# PCB-BI16-2x8.net
KiCad netlist of a schematic drawn in EAGLE
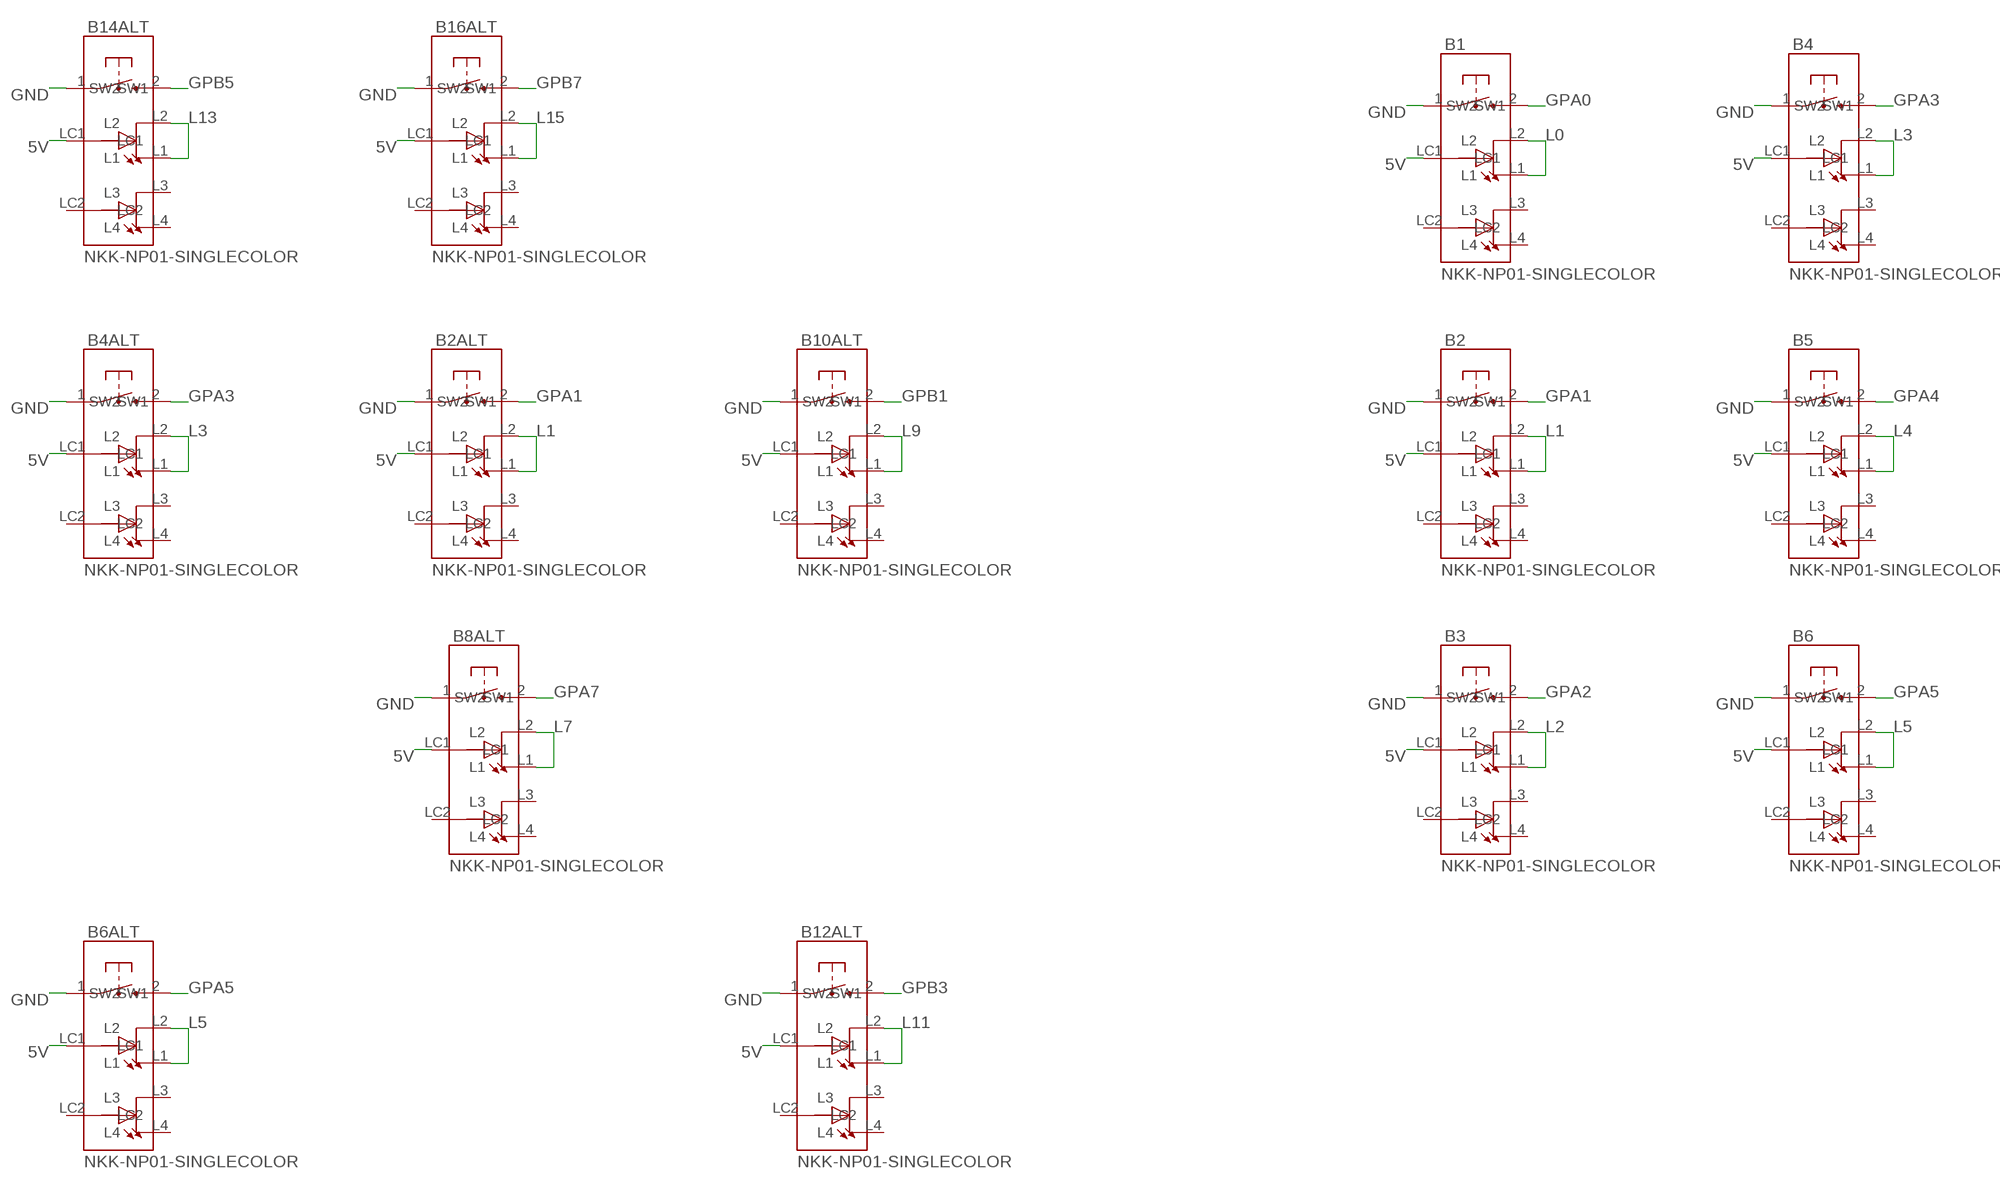
[diagram p0: schematic, sheet 1, part 1 of 2]
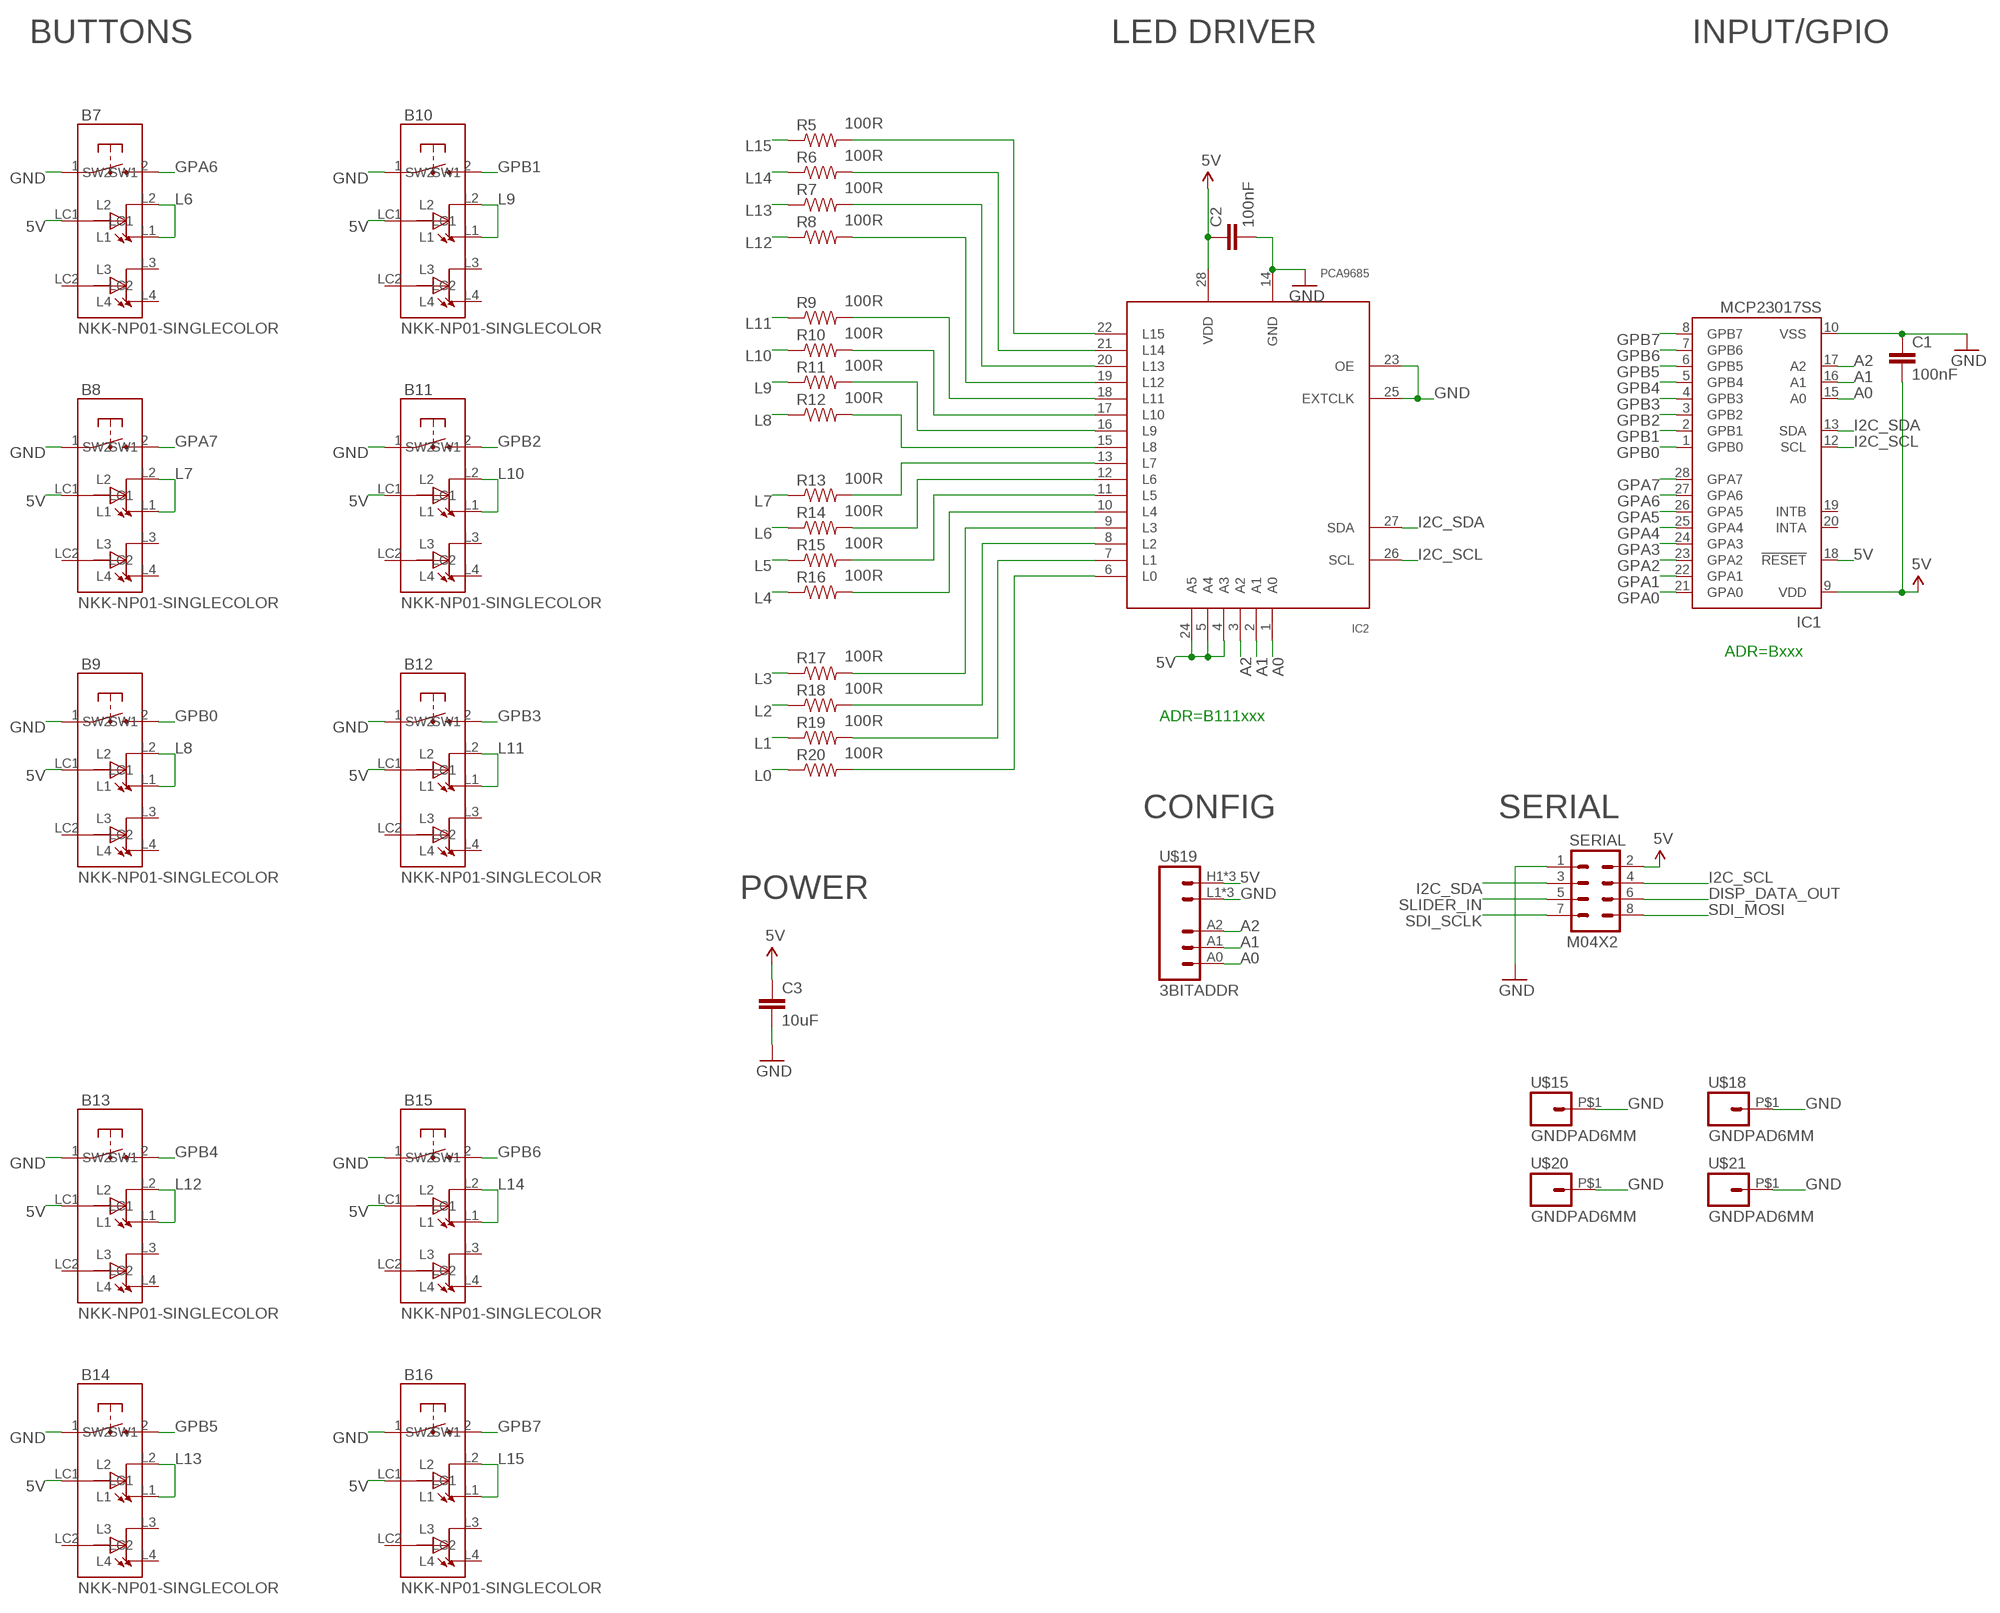
[diagram p1: schematic, sheet 1, part 2 of 2]

(export (version "E")
  (design (tool "Eeschema 10.0.6"))
  (components
    (comp (ref "B1")
      (value "NKK-NP01-SINGLECOLOR")
      (footprint "eagle-import:NKK-NP01")
      (libsource (lib "eagle-import") (part "NKK-NP01-SINGLECOLOR"))
    )
    (comp (ref "B2")
      (value "NKK-NP01-SINGLECOLOR")
      (footprint "eagle-import:NKK-NP01")
      (libsource (lib "eagle-import") (part "NKK-NP01-SINGLECOLOR"))
    )
    (comp (ref "B2ALT")
      (value "NKK-NP01-SINGLECOLOR")
      (footprint "eagle-import:NKK-NP01")
      (libsource (lib "eagle-import") (part "NKK-NP01-SINGLECOLOR"))
    )
    (comp (ref "B3")
      (value "NKK-NP01-SINGLECOLOR")
      (footprint "eagle-import:NKK-NP01")
      (libsource (lib "eagle-import") (part "NKK-NP01-SINGLECOLOR"))
    )
    (comp (ref "B4")
      (value "NKK-NP01-SINGLECOLOR")
      (footprint "eagle-import:NKK-NP01")
      (libsource (lib "eagle-import") (part "NKK-NP01-SINGLECOLOR"))
    )
    (comp (ref "B4ALT")
      (value "NKK-NP01-SINGLECOLOR")
      (footprint "eagle-import:NKK-NP01")
      (libsource (lib "eagle-import") (part "NKK-NP01-SINGLECOLOR"))
    )
    (comp (ref "B5")
      (value "NKK-NP01-SINGLECOLOR")
      (footprint "eagle-import:NKK-NP01")
      (libsource (lib "eagle-import") (part "NKK-NP01-SINGLECOLOR"))
    )
    (comp (ref "B6")
      (value "NKK-NP01-SINGLECOLOR")
      (footprint "eagle-import:NKK-NP01")
      (libsource (lib "eagle-import") (part "NKK-NP01-SINGLECOLOR"))
    )
    (comp (ref "B6ALT")
      (value "NKK-NP01-SINGLECOLOR")
      (footprint "eagle-import:NKK-NP01")
      (libsource (lib "eagle-import") (part "NKK-NP01-SINGLECOLOR"))
    )
    (comp (ref "B7")
      (value "NKK-NP01-SINGLECOLOR")
      (footprint "eagle-import:NKK-NP01")
      (libsource (lib "eagle-import") (part "NKK-NP01-SINGLECOLOR"))
    )
    (comp (ref "B8")
      (value "NKK-NP01-SINGLECOLOR")
      (footprint "eagle-import:NKK-NP01")
      (libsource (lib "eagle-import") (part "NKK-NP01-SINGLECOLOR"))
    )
    (comp (ref "B8ALT")
      (value "NKK-NP01-SINGLECOLOR")
      (footprint "eagle-import:NKK-NP01")
      (libsource (lib "eagle-import") (part "NKK-NP01-SINGLECOLOR"))
    )
    (comp (ref "B9")
      (value "NKK-NP01-SINGLECOLOR")
      (footprint "eagle-import:NKK-NP01")
      (libsource (lib "eagle-import") (part "NKK-NP01-SINGLECOLOR"))
    )
    (comp (ref "B10")
      (value "NKK-NP01-SINGLECOLOR")
      (footprint "eagle-import:NKK-NP01")
      (libsource (lib "eagle-import") (part "NKK-NP01-SINGLECOLOR"))
    )
    (comp (ref "B10ALT")
      (value "NKK-NP01-SINGLECOLOR")
      (footprint "eagle-import:NKK-NP01")
      (libsource (lib "eagle-import") (part "NKK-NP01-SINGLECOLOR"))
    )
    (comp (ref "B11")
      (value "NKK-NP01-SINGLECOLOR")
      (footprint "eagle-import:NKK-NP01")
      (libsource (lib "eagle-import") (part "NKK-NP01-SINGLECOLOR"))
    )
    (comp (ref "B12")
      (value "NKK-NP01-SINGLECOLOR")
      (footprint "eagle-import:NKK-NP01")
      (libsource (lib "eagle-import") (part "NKK-NP01-SINGLECOLOR"))
    )
    (comp (ref "B12ALT")
      (value "NKK-NP01-SINGLECOLOR")
      (footprint "eagle-import:NKK-NP01")
      (libsource (lib "eagle-import") (part "NKK-NP01-SINGLECOLOR"))
    )
    (comp (ref "B13")
      (value "NKK-NP01-SINGLECOLOR")
      (footprint "eagle-import:NKK-NP01")
      (libsource (lib "eagle-import") (part "NKK-NP01-SINGLECOLOR"))
    )
    (comp (ref "B14")
      (value "NKK-NP01-SINGLECOLOR")
      (footprint "eagle-import:NKK-NP01")
      (libsource (lib "eagle-import") (part "NKK-NP01-SINGLECOLOR"))
    )
    (comp (ref "B14ALT")
      (value "NKK-NP01-SINGLECOLOR")
      (footprint "eagle-import:NKK-NP01")
      (libsource (lib "eagle-import") (part "NKK-NP01-SINGLECOLOR"))
    )
    (comp (ref "B15")
      (value "NKK-NP01-SINGLECOLOR")
      (footprint "eagle-import:NKK-NP01")
      (libsource (lib "eagle-import") (part "NKK-NP01-SINGLECOLOR"))
    )
    (comp (ref "B16")
      (value "NKK-NP01-SINGLECOLOR")
      (footprint "eagle-import:NKK-NP01")
      (libsource (lib "eagle-import") (part "NKK-NP01-SINGLECOLOR"))
    )
    (comp (ref "B16ALT")
      (value "NKK-NP01-SINGLECOLOR")
      (footprint "eagle-import:NKK-NP01")
      (libsource (lib "eagle-import") (part "NKK-NP01-SINGLECOLOR"))
    )
    (comp (ref "C1")
      (value "100nF")
      (footprint "eagle-import:0603-CAP")
      (libsource (lib "eagle-import") (part "CAP0603-CAP"))
    )
    (comp (ref "C2")
      (value "100nF")
      (footprint "eagle-import:0603-CAP")
      (libsource (lib "eagle-import") (part "CAP0603-CAP"))
    )
    (comp (ref "C3")
      (value "10uF")
      (footprint "eagle-import:0805")
      (libsource (lib "eagle-import") (part "CAP0805"))
    )
    (comp (ref "IC1")
      (value "MCP23017SS")
      (footprint "eagle-import:SSOP28")
      (fields
        (field (name "MF") "MICROCHIP")
        (field (name "MPN") "MCP23017-E/SS")
        (field (name "MPN_1") "MCP23017-E/SS")
        (field (name "OC_FARNELL") "1467674")
        (field (name "OC_NEWARK") "31K2960")
      )
      (libsource (lib "eagle-import") (part "MCP23017SS"))
    )
    (comp (ref "IC2")
      (value "PCA9685")
      (footprint "eagle-import:TSSOP28")
      (libsource (lib "eagle-import") (part "PCA9685"))
    )
    (comp (ref "R5")
      (value "100R")
      (footprint "eagle-import:0603-RES")
      (libsource (lib "eagle-import") (part "RESISTOR0603-RES"))
    )
    (comp (ref "R6")
      (value "100R")
      (footprint "eagle-import:0603-RES")
      (libsource (lib "eagle-import") (part "RESISTOR0603-RES"))
    )
    (comp (ref "R7")
      (value "100R")
      (footprint "eagle-import:0603-RES")
      (libsource (lib "eagle-import") (part "RESISTOR0603-RES"))
    )
    (comp (ref "R8")
      (value "100R")
      (footprint "eagle-import:0603-RES")
      (libsource (lib "eagle-import") (part "RESISTOR0603-RES"))
    )
    (comp (ref "R9")
      (value "100R")
      (footprint "eagle-import:0603-RES")
      (libsource (lib "eagle-import") (part "RESISTOR0603-RES"))
    )
    (comp (ref "R10")
      (value "100R")
      (footprint "eagle-import:0603-RES")
      (libsource (lib "eagle-import") (part "RESISTOR0603-RES"))
    )
    (comp (ref "R11")
      (value "100R")
      (footprint "eagle-import:0603-RES")
      (libsource (lib "eagle-import") (part "RESISTOR0603-RES"))
    )
    (comp (ref "R12")
      (value "100R")
      (footprint "eagle-import:0603-RES")
      (libsource (lib "eagle-import") (part "RESISTOR0603-RES"))
    )
    (comp (ref "R13")
      (value "100R")
      (footprint "eagle-import:0603-RES")
      (libsource (lib "eagle-import") (part "RESISTOR0603-RES"))
    )
    (comp (ref "R14")
      (value "100R")
      (footprint "eagle-import:0603-RES")
      (libsource (lib "eagle-import") (part "RESISTOR0603-RES"))
    )
    (comp (ref "R15")
      (value "100R")
      (footprint "eagle-import:0603-RES")
      (libsource (lib "eagle-import") (part "RESISTOR0603-RES"))
    )
    (comp (ref "R16")
      (value "100R")
      (footprint "eagle-import:0603-RES")
      (libsource (lib "eagle-import") (part "RESISTOR0603-RES"))
    )
    (comp (ref "R17")
      (value "100R")
      (footprint "eagle-import:0603-RES")
      (libsource (lib "eagle-import") (part "RESISTOR0603-RES"))
    )
    (comp (ref "R18")
      (value "100R")
      (footprint "eagle-import:0603-RES")
      (libsource (lib "eagle-import") (part "RESISTOR0603-RES"))
    )
    (comp (ref "R19")
      (value "100R")
      (footprint "eagle-import:0603-RES")
      (libsource (lib "eagle-import") (part "RESISTOR0603-RES"))
    )
    (comp (ref "R20")
      (value "100R")
      (footprint "eagle-import:0603-RES")
      (libsource (lib "eagle-import") (part "RESISTOR0603-RES"))
    )
    (comp (ref "SERIAL")
      (value "M04X2")
      (footprint "eagle-import:2X4")
      (libsource (lib "eagle-import") (part "M04X2"))
    )
    (comp (ref "U$15")
      (value "GNDPAD6MM")
      (footprint "eagle-import:3.2MMPAD6MM")
      (libsource (lib "eagle-import") (part "GNDPAD6MM"))
    )
    (comp (ref "U$18")
      (value "GNDPAD6MM")
      (footprint "eagle-import:3.2MMPAD6MM")
      (libsource (lib "eagle-import") (part "GNDPAD6MM"))
    )
    (comp (ref "U$19")
      (value "3BITADDR")
      (footprint "eagle-import:3BITADDR")
      (libsource (lib "eagle-import") (part "3BITADDR"))
    )
    (comp (ref "U$20")
      (value "GNDPAD6MM")
      (footprint "eagle-import:3.2MMPAD6MM")
      (libsource (lib "eagle-import") (part "GNDPAD6MM"))
    )
    (comp (ref "U$21")
      (value "GNDPAD6MM")
      (footprint "eagle-import:3.2MMPAD6MM")
      (libsource (lib "eagle-import") (part "GNDPAD6MM"))
    )
  )
  (nets
    (net (code "1") (name "5V") (class "Default")
      (node (ref "B1") (pin "LC1") (pinfunction "LC1_LC1") (pintype "bidirectional"))
      (node (ref "B10") (pin "LC1") (pinfunction "LC1_LC1") (pintype "bidirectional"))
      (node (ref "B10ALT") (pin "LC1") (pinfunction "LC1_LC1") (pintype "bidirectional"))
      (node (ref "B11") (pin "LC1") (pinfunction "LC1_LC1") (pintype "bidirectional"))
      (node (ref "B12") (pin "LC1") (pinfunction "LC1_LC1") (pintype "bidirectional"))
      (node (ref "B12ALT") (pin "LC1") (pinfunction "LC1_LC1") (pintype "bidirectional"))
      (node (ref "B13") (pin "LC1") (pinfunction "LC1_LC1") (pintype "bidirectional"))
      (node (ref "B14") (pin "LC1") (pinfunction "LC1_LC1") (pintype "bidirectional"))
      (node (ref "B14ALT") (pin "LC1") (pinfunction "LC1_LC1") (pintype "bidirectional"))
      (node (ref "B15") (pin "LC1") (pinfunction "LC1_LC1") (pintype "bidirectional"))
      (node (ref "B16") (pin "LC1") (pinfunction "LC1_LC1") (pintype "bidirectional"))
      (node (ref "B16ALT") (pin "LC1") (pinfunction "LC1_LC1") (pintype "bidirectional"))
      (node (ref "B2") (pin "LC1") (pinfunction "LC1_LC1") (pintype "bidirectional"))
      (node (ref "B2ALT") (pin "LC1") (pinfunction "LC1_LC1") (pintype "bidirectional"))
      (node (ref "B3") (pin "LC1") (pinfunction "LC1_LC1") (pintype "bidirectional"))
      (node (ref "B4") (pin "LC1") (pinfunction "LC1_LC1") (pintype "bidirectional"))
      (node (ref "B4ALT") (pin "LC1") (pinfunction "LC1_LC1") (pintype "bidirectional"))
      (node (ref "B5") (pin "LC1") (pinfunction "LC1_LC1") (pintype "bidirectional"))
      (node (ref "B6") (pin "LC1") (pinfunction "LC1_LC1") (pintype "bidirectional"))
      (node (ref "B6ALT") (pin "LC1") (pinfunction "LC1_LC1") (pintype "bidirectional"))
      (node (ref "B7") (pin "LC1") (pinfunction "LC1_LC1") (pintype "bidirectional"))
      (node (ref "B8") (pin "LC1") (pinfunction "LC1_LC1") (pintype "bidirectional"))
      (node (ref "B8ALT") (pin "LC1") (pinfunction "LC1_LC1") (pintype "bidirectional"))
      (node (ref "B9") (pin "LC1") (pinfunction "LC1_LC1") (pintype "bidirectional"))
      (node (ref "C1") (pin "2") (pinfunction "2_2") (pintype "passive"))
      (node (ref "C2") (pin "1") (pinfunction "1_1") (pintype "passive"))
      (node (ref "C3") (pin "1") (pinfunction "1_1") (pintype "passive"))
      (node (ref "IC1") (pin "18") (pinfunction "~{RESET}_18") (pintype "input"))
      (node (ref "IC1") (pin "9") (pinfunction "VDD_9") (pintype "power_in"))
      (node (ref "IC2") (pin "24") (pinfunction "A5_24") (pintype "input"))
      (node (ref "IC2") (pin "28") (pinfunction "VDD_28") (pintype "power_in"))
      (node (ref "IC2") (pin "4") (pinfunction "A3_4") (pintype "input"))
      (node (ref "IC2") (pin "5") (pinfunction "A4_5") (pintype "input"))
      (node (ref "SERIAL") (pin "2") (pinfunction "2_2") (pintype "passive"))
      (node (ref "U$19") (pin "H1") (pinfunction "VCC_H1") (pintype "passive"))
      (node (ref "U$19") (pin "H2") (pinfunction "VCC_H2") (pintype "passive"))
      (node (ref "U$19") (pin "H3") (pinfunction "VCC_H3") (pintype "passive"))
    )
    (net (code "2") (name "A0") (class "Default")
      (node (ref "IC1") (pin "15") (pinfunction "A0_15") (pintype "input"))
      (node (ref "IC2") (pin "1") (pinfunction "A0_1") (pintype "input"))
      (node (ref "U$19") (pin "A0") (pinfunction "A0_A0") (pintype "passive"))
    )
    (net (code "3") (name "A1") (class "Default")
      (node (ref "IC1") (pin "16") (pinfunction "A1_16") (pintype "input"))
      (node (ref "IC2") (pin "2") (pinfunction "A1_2") (pintype "input"))
      (node (ref "U$19") (pin "A1") (pinfunction "A1_A1") (pintype "passive"))
    )
    (net (code "4") (name "A2") (class "Default")
      (node (ref "IC1") (pin "17") (pinfunction "A2_17") (pintype "input"))
      (node (ref "IC2") (pin "3") (pinfunction "A2_3") (pintype "input"))
      (node (ref "U$19") (pin "A2") (pinfunction "A2_A2") (pintype "passive"))
    )
    (net (code "5") (name "DISP_DATA_OUT") (class "Default")
      (node (ref "SERIAL") (pin "6") (pinfunction "6_6") (pintype "passive"))
    )
    (net (code "6") (name "GND") (class "Default")
      (node (ref "B1") (pin "1") (pinfunction "SW1_1") (pintype "bidirectional"))
      (node (ref "B10") (pin "1") (pinfunction "SW1_1") (pintype "bidirectional"))
      (node (ref "B10ALT") (pin "1") (pinfunction "SW1_1") (pintype "bidirectional"))
      (node (ref "B11") (pin "1") (pinfunction "SW1_1") (pintype "bidirectional"))
      (node (ref "B12") (pin "1") (pinfunction "SW1_1") (pintype "bidirectional"))
      (node (ref "B12ALT") (pin "1") (pinfunction "SW1_1") (pintype "bidirectional"))
      (node (ref "B13") (pin "1") (pinfunction "SW1_1") (pintype "bidirectional"))
      (node (ref "B14") (pin "1") (pinfunction "SW1_1") (pintype "bidirectional"))
      (node (ref "B14ALT") (pin "1") (pinfunction "SW1_1") (pintype "bidirectional"))
      (node (ref "B15") (pin "1") (pinfunction "SW1_1") (pintype "bidirectional"))
      (node (ref "B16") (pin "1") (pinfunction "SW1_1") (pintype "bidirectional"))
      (node (ref "B16ALT") (pin "1") (pinfunction "SW1_1") (pintype "bidirectional"))
      (node (ref "B2") (pin "1") (pinfunction "SW1_1") (pintype "bidirectional"))
      (node (ref "B2ALT") (pin "1") (pinfunction "SW1_1") (pintype "bidirectional"))
      (node (ref "B3") (pin "1") (pinfunction "SW1_1") (pintype "bidirectional"))
      (node (ref "B4") (pin "1") (pinfunction "SW1_1") (pintype "bidirectional"))
      (node (ref "B4ALT") (pin "1") (pinfunction "SW1_1") (pintype "bidirectional"))
      (node (ref "B5") (pin "1") (pinfunction "SW1_1") (pintype "bidirectional"))
      (node (ref "B6") (pin "1") (pinfunction "SW1_1") (pintype "bidirectional"))
      (node (ref "B6ALT") (pin "1") (pinfunction "SW1_1") (pintype "bidirectional"))
      (node (ref "B7") (pin "1") (pinfunction "SW1_1") (pintype "bidirectional"))
      (node (ref "B8") (pin "1") (pinfunction "SW1_1") (pintype "bidirectional"))
      (node (ref "B8ALT") (pin "1") (pinfunction "SW1_1") (pintype "bidirectional"))
      (node (ref "B9") (pin "1") (pinfunction "SW1_1") (pintype "bidirectional"))
      (node (ref "C1") (pin "1") (pinfunction "1_1") (pintype "passive"))
      (node (ref "C2") (pin "2") (pinfunction "2_2") (pintype "passive"))
      (node (ref "C3") (pin "2") (pinfunction "2_2") (pintype "passive"))
      (node (ref "IC1") (pin "10") (pinfunction "VSS_10") (pintype "power_in"))
      (node (ref "IC2") (pin "14") (pinfunction "GND_14") (pintype "power_in"))
      (node (ref "IC2") (pin "23") (pinfunction "OE_23") (pintype "input"))
      (node (ref "IC2") (pin "25") (pinfunction "EXTCLK_25") (pintype "input"))
      (node (ref "SERIAL") (pin "1") (pinfunction "1_1") (pintype "passive"))
      (node (ref "U$15") (pin "P$1") (pinfunction "1_P$1") (pintype "passive"))
      (node (ref "U$18") (pin "P$1") (pinfunction "1_P$1") (pintype "passive"))
      (node (ref "U$19") (pin "L1") (pinfunction "GND_L1") (pintype "passive"))
      (node (ref "U$19") (pin "L2") (pinfunction "GND_L2") (pintype "passive"))
      (node (ref "U$19") (pin "L3") (pinfunction "GND_L3") (pintype "passive"))
      (node (ref "U$20") (pin "P$1") (pinfunction "1_P$1") (pintype "passive"))
      (node (ref "U$21") (pin "P$1") (pinfunction "1_P$1") (pintype "passive"))
    )
    (net (code "7") (name "GPA0") (class "Default")
      (node (ref "B1") (pin "2") (pinfunction "SW2_2") (pintype "bidirectional"))
      (node (ref "IC1") (pin "21") (pinfunction "GPA0_21") (pintype "bidirectional"))
    )
    (net (code "8") (name "GPA1") (class "Default")
      (node (ref "B2") (pin "2") (pinfunction "SW2_2") (pintype "bidirectional"))
      (node (ref "B2ALT") (pin "2") (pinfunction "SW2_2") (pintype "bidirectional"))
      (node (ref "IC1") (pin "22") (pinfunction "GPA1_22") (pintype "bidirectional"))
    )
    (net (code "9") (name "GPA2") (class "Default")
      (node (ref "B3") (pin "2") (pinfunction "SW2_2") (pintype "bidirectional"))
      (node (ref "IC1") (pin "23") (pinfunction "GPA2_23") (pintype "bidirectional"))
    )
    (net (code "10") (name "GPA3") (class "Default")
      (node (ref "B4") (pin "2") (pinfunction "SW2_2") (pintype "bidirectional"))
      (node (ref "B4ALT") (pin "2") (pinfunction "SW2_2") (pintype "bidirectional"))
      (node (ref "IC1") (pin "24") (pinfunction "GPA3_24") (pintype "bidirectional"))
    )
    (net (code "11") (name "GPA4") (class "Default")
      (node (ref "B5") (pin "2") (pinfunction "SW2_2") (pintype "bidirectional"))
      (node (ref "IC1") (pin "25") (pinfunction "GPA4_25") (pintype "bidirectional"))
    )
    (net (code "12") (name "GPA5") (class "Default")
      (node (ref "B6") (pin "2") (pinfunction "SW2_2") (pintype "bidirectional"))
      (node (ref "B6ALT") (pin "2") (pinfunction "SW2_2") (pintype "bidirectional"))
      (node (ref "IC1") (pin "26") (pinfunction "GPA5_26") (pintype "bidirectional"))
    )
    (net (code "13") (name "GPA6") (class "Default")
      (node (ref "B7") (pin "2") (pinfunction "SW2_2") (pintype "bidirectional"))
      (node (ref "IC1") (pin "27") (pinfunction "GPA6_27") (pintype "bidirectional"))
    )
    (net (code "14") (name "GPA7") (class "Default")
      (node (ref "B8") (pin "2") (pinfunction "SW2_2") (pintype "bidirectional"))
      (node (ref "B8ALT") (pin "2") (pinfunction "SW2_2") (pintype "bidirectional"))
      (node (ref "IC1") (pin "28") (pinfunction "GPA7_28") (pintype "bidirectional"))
    )
    (net (code "15") (name "GPB0") (class "Default")
      (node (ref "B9") (pin "2") (pinfunction "SW2_2") (pintype "bidirectional"))
      (node (ref "IC1") (pin "1") (pinfunction "GPB0_1") (pintype "bidirectional"))
    )
    (net (code "16") (name "GPB1") (class "Default")
      (node (ref "B10") (pin "2") (pinfunction "SW2_2") (pintype "bidirectional"))
      (node (ref "B10ALT") (pin "2") (pinfunction "SW2_2") (pintype "bidirectional"))
      (node (ref "IC1") (pin "2") (pinfunction "GPB1_2") (pintype "bidirectional"))
    )
    (net (code "17") (name "GPB2") (class "Default")
      (node (ref "B11") (pin "2") (pinfunction "SW2_2") (pintype "bidirectional"))
      (node (ref "IC1") (pin "3") (pinfunction "GPB2_3") (pintype "bidirectional"))
    )
    (net (code "18") (name "GPB3") (class "Default")
      (node (ref "B12") (pin "2") (pinfunction "SW2_2") (pintype "bidirectional"))
      (node (ref "B12ALT") (pin "2") (pinfunction "SW2_2") (pintype "bidirectional"))
      (node (ref "IC1") (pin "4") (pinfunction "GPB3_4") (pintype "bidirectional"))
    )
    (net (code "19") (name "GPB4") (class "Default")
      (node (ref "B13") (pin "2") (pinfunction "SW2_2") (pintype "bidirectional"))
      (node (ref "IC1") (pin "5") (pinfunction "GPB4_5") (pintype "bidirectional"))
    )
    (net (code "20") (name "GPB5") (class "Default")
      (node (ref "B14") (pin "2") (pinfunction "SW2_2") (pintype "bidirectional"))
      (node (ref "B14ALT") (pin "2") (pinfunction "SW2_2") (pintype "bidirectional"))
      (node (ref "IC1") (pin "6") (pinfunction "GPB5_6") (pintype "bidirectional"))
    )
    (net (code "21") (name "GPB6") (class "Default")
      (node (ref "B15") (pin "2") (pinfunction "SW2_2") (pintype "bidirectional"))
      (node (ref "IC1") (pin "7") (pinfunction "GPB6_7") (pintype "bidirectional"))
    )
    (net (code "22") (name "GPB7") (class "Default")
      (node (ref "B16") (pin "2") (pinfunction "SW2_2") (pintype "bidirectional"))
      (node (ref "B16ALT") (pin "2") (pinfunction "SW2_2") (pintype "bidirectional"))
      (node (ref "IC1") (pin "8") (pinfunction "GPB7_8") (pintype "bidirectional"))
    )
    (net (code "23") (name "I2C_SCL") (class "Default")
      (node (ref "IC1") (pin "12") (pinfunction "SCL_12") (pintype "input"))
      (node (ref "IC2") (pin "26") (pinfunction "SCL_26") (pintype "input"))
      (node (ref "SERIAL") (pin "4") (pinfunction "4_4") (pintype "passive"))
    )
    (net (code "24") (name "I2C_SDA") (class "Default")
      (node (ref "IC1") (pin "13") (pinfunction "SDA_13") (pintype "bidirectional"))
      (node (ref "IC2") (pin "27") (pinfunction "SDA_27") (pintype "input"))
      (node (ref "SERIAL") (pin "3") (pinfunction "3_3") (pintype "passive"))
    )
    (net (code "25") (name "L0") (class "Default")
      (node (ref "B1") (pin "L1") (pinfunction "L1_L1") (pintype "bidirectional"))
      (node (ref "B1") (pin "L2") (pinfunction "L2_L2") (pintype "bidirectional"))
      (node (ref "R20") (pin "1") (pinfunction "1_1") (pintype "passive"))
    )
    (net (code "26") (name "L1") (class "Default")
      (node (ref "B2") (pin "L1") (pinfunction "L1_L1") (pintype "bidirectional"))
      (node (ref "B2") (pin "L2") (pinfunction "L2_L2") (pintype "bidirectional"))
      (node (ref "B2ALT") (pin "L1") (pinfunction "L1_L1") (pintype "bidirectional"))
      (node (ref "B2ALT") (pin "L2") (pinfunction "L2_L2") (pintype "bidirectional"))
      (node (ref "R19") (pin "1") (pinfunction "1_1") (pintype "passive"))
    )
    (net (code "27") (name "L2") (class "Default")
      (node (ref "B3") (pin "L1") (pinfunction "L1_L1") (pintype "bidirectional"))
      (node (ref "B3") (pin "L2") (pinfunction "L2_L2") (pintype "bidirectional"))
      (node (ref "R18") (pin "1") (pinfunction "1_1") (pintype "passive"))
    )
    (net (code "28") (name "L3") (class "Default")
      (node (ref "B4") (pin "L1") (pinfunction "L1_L1") (pintype "bidirectional"))
      (node (ref "B4") (pin "L2") (pinfunction "L2_L2") (pintype "bidirectional"))
      (node (ref "B4ALT") (pin "L1") (pinfunction "L1_L1") (pintype "bidirectional"))
      (node (ref "B4ALT") (pin "L2") (pinfunction "L2_L2") (pintype "bidirectional"))
      (node (ref "R17") (pin "1") (pinfunction "1_1") (pintype "passive"))
    )
    (net (code "29") (name "L4") (class "Default")
      (node (ref "B5") (pin "L1") (pinfunction "L1_L1") (pintype "bidirectional"))
      (node (ref "B5") (pin "L2") (pinfunction "L2_L2") (pintype "bidirectional"))
      (node (ref "R16") (pin "1") (pinfunction "1_1") (pintype "passive"))
    )
    (net (code "30") (name "L5") (class "Default")
      (node (ref "B6") (pin "L1") (pinfunction "L1_L1") (pintype "bidirectional"))
      (node (ref "B6") (pin "L2") (pinfunction "L2_L2") (pintype "bidirectional"))
      (node (ref "B6ALT") (pin "L1") (pinfunction "L1_L1") (pintype "bidirectional"))
      (node (ref "B6ALT") (pin "L2") (pinfunction "L2_L2") (pintype "bidirectional"))
      (node (ref "R15") (pin "1") (pinfunction "1_1") (pintype "passive"))
    )
    (net (code "31") (name "L6") (class "Default")
      (node (ref "B7") (pin "L1") (pinfunction "L1_L1") (pintype "bidirectional"))
      (node (ref "B7") (pin "L2") (pinfunction "L2_L2") (pintype "bidirectional"))
      (node (ref "R14") (pin "1") (pinfunction "1_1") (pintype "passive"))
    )
    (net (code "32") (name "L7") (class "Default")
      (node (ref "B8") (pin "L1") (pinfunction "L1_L1") (pintype "bidirectional"))
      (node (ref "B8") (pin "L2") (pinfunction "L2_L2") (pintype "bidirectional"))
      (node (ref "B8ALT") (pin "L1") (pinfunction "L1_L1") (pintype "bidirectional"))
      (node (ref "B8ALT") (pin "L2") (pinfunction "L2_L2") (pintype "bidirectional"))
      (node (ref "R13") (pin "1") (pinfunction "1_1") (pintype "passive"))
    )
    (net (code "33") (name "L8") (class "Default")
      (node (ref "B9") (pin "L1") (pinfunction "L1_L1") (pintype "bidirectional"))
      (node (ref "B9") (pin "L2") (pinfunction "L2_L2") (pintype "bidirectional"))
      (node (ref "R12") (pin "1") (pinfunction "1_1") (pintype "passive"))
    )
    (net (code "34") (name "L9") (class "Default")
      (node (ref "B10") (pin "L1") (pinfunction "L1_L1") (pintype "bidirectional"))
      (node (ref "B10") (pin "L2") (pinfunction "L2_L2") (pintype "bidirectional"))
      (node (ref "B10ALT") (pin "L1") (pinfunction "L1_L1") (pintype "bidirectional"))
      (node (ref "B10ALT") (pin "L2") (pinfunction "L2_L2") (pintype "bidirectional"))
      (node (ref "R11") (pin "1") (pinfunction "1_1") (pintype "passive"))
    )
    (net (code "35") (name "L10") (class "Default")
      (node (ref "B11") (pin "L1") (pinfunction "L1_L1") (pintype "bidirectional"))
      (node (ref "B11") (pin "L2") (pinfunction "L2_L2") (pintype "bidirectional"))
      (node (ref "R10") (pin "1") (pinfunction "1_1") (pintype "passive"))
    )
    (net (code "36") (name "L11") (class "Default")
      (node (ref "B12") (pin "L1") (pinfunction "L1_L1") (pintype "bidirectional"))
      (node (ref "B12") (pin "L2") (pinfunction "L2_L2") (pintype "bidirectional"))
      (node (ref "B12ALT") (pin "L1") (pinfunction "L1_L1") (pintype "bidirectional"))
      (node (ref "B12ALT") (pin "L2") (pinfunction "L2_L2") (pintype "bidirectional"))
      (node (ref "R9") (pin "1") (pinfunction "1_1") (pintype "passive"))
    )
    (net (code "37") (name "L12") (class "Default")
      (node (ref "B13") (pin "L1") (pinfunction "L1_L1") (pintype "bidirectional"))
      (node (ref "B13") (pin "L2") (pinfunction "L2_L2") (pintype "bidirectional"))
      (node (ref "R8") (pin "1") (pinfunction "1_1") (pintype "passive"))
    )
    (net (code "38") (name "L13") (class "Default")
      (node (ref "B14") (pin "L1") (pinfunction "L1_L1") (pintype "bidirectional"))
      (node (ref "B14") (pin "L2") (pinfunction "L2_L2") (pintype "bidirectional"))
      (node (ref "B14ALT") (pin "L1") (pinfunction "L1_L1") (pintype "bidirectional"))
      (node (ref "B14ALT") (pin "L2") (pinfunction "L2_L2") (pintype "bidirectional"))
      (node (ref "R7") (pin "1") (pinfunction "1_1") (pintype "passive"))
    )
    (net (code "39") (name "L14") (class "Default")
      (node (ref "B15") (pin "L1") (pinfunction "L1_L1") (pintype "bidirectional"))
      (node (ref "B15") (pin "L2") (pinfunction "L2_L2") (pintype "bidirectional"))
      (node (ref "R6") (pin "1") (pinfunction "1_1") (pintype "passive"))
    )
    (net (code "40") (name "L15") (class "Default")
      (node (ref "B16") (pin "L1") (pinfunction "L1_L1") (pintype "bidirectional"))
      (node (ref "B16") (pin "L2") (pinfunction "L2_L2") (pintype "bidirectional"))
      (node (ref "B16ALT") (pin "L1") (pinfunction "L1_L1") (pintype "bidirectional"))
      (node (ref "B16ALT") (pin "L2") (pinfunction "L2_L2") (pintype "bidirectional"))
      (node (ref "R5") (pin "1") (pinfunction "1_1") (pintype "passive"))
    )
    (net (code "41") (name "Net-(IC2-L0)") (class "Default")
      (node (ref "IC2") (pin "6") (pinfunction "L0_6") (pintype "output"))
      (node (ref "R20") (pin "2") (pinfunction "2_2") (pintype "passive"))
    )
    (net (code "42") (name "Net-(IC2-L1)") (class "Default")
      (node (ref "IC2") (pin "7") (pinfunction "L1_7") (pintype "output"))
      (node (ref "R19") (pin "2") (pinfunction "2_2") (pintype "passive"))
    )
    (net (code "43") (name "Net-(IC2-L2)") (class "Default")
      (node (ref "IC2") (pin "8") (pinfunction "L2_8") (pintype "output"))
      (node (ref "R18") (pin "2") (pinfunction "2_2") (pintype "passive"))
    )
    (net (code "44") (name "Net-(IC2-L3)") (class "Default")
      (node (ref "IC2") (pin "9") (pinfunction "L3_9") (pintype "output"))
      (node (ref "R17") (pin "2") (pinfunction "2_2") (pintype "passive"))
    )
    (net (code "45") (name "Net-(IC2-L4)") (class "Default")
      (node (ref "IC2") (pin "10") (pinfunction "L4_10") (pintype "output"))
      (node (ref "R16") (pin "2") (pinfunction "2_2") (pintype "passive"))
    )
    (net (code "46") (name "Net-(IC2-L5)") (class "Default")
      (node (ref "IC2") (pin "11") (pinfunction "L5_11") (pintype "output"))
      (node (ref "R15") (pin "2") (pinfunction "2_2") (pintype "passive"))
    )
    (net (code "47") (name "Net-(IC2-L6)") (class "Default")
      (node (ref "IC2") (pin "12") (pinfunction "L6_12") (pintype "output"))
      (node (ref "R14") (pin "2") (pinfunction "2_2") (pintype "passive"))
    )
    (net (code "48") (name "Net-(IC2-L7)") (class "Default")
      (node (ref "IC2") (pin "13") (pinfunction "L7_13") (pintype "output"))
      (node (ref "R13") (pin "2") (pinfunction "2_2") (pintype "passive"))
    )
    (net (code "49") (name "Net-(IC2-L8)") (class "Default")
      (node (ref "IC2") (pin "15") (pinfunction "L8_15") (pintype "output"))
      (node (ref "R12") (pin "2") (pinfunction "2_2") (pintype "passive"))
    )
    (net (code "50") (name "Net-(IC2-L9)") (class "Default")
      (node (ref "IC2") (pin "16") (pinfunction "L9_16") (pintype "output"))
      (node (ref "R11") (pin "2") (pinfunction "2_2") (pintype "passive"))
    )
    (net (code "51") (name "Net-(IC2-L10)") (class "Default")
      (node (ref "IC2") (pin "17") (pinfunction "L10_17") (pintype "output"))
      (node (ref "R10") (pin "2") (pinfunction "2_2") (pintype "passive"))
    )
    (net (code "52") (name "Net-(IC2-L11)") (class "Default")
      (node (ref "IC2") (pin "18") (pinfunction "L11_18") (pintype "output"))
      (node (ref "R9") (pin "2") (pinfunction "2_2") (pintype "passive"))
    )
    (net (code "53") (name "Net-(IC2-L12)") (class "Default")
      (node (ref "IC2") (pin "19") (pinfunction "L12_19") (pintype "output"))
      (node (ref "R8") (pin "2") (pinfunction "2_2") (pintype "passive"))
    )
    (net (code "54") (name "Net-(IC2-L13)") (class "Default")
      (node (ref "IC2") (pin "20") (pinfunction "L13_20") (pintype "output"))
      (node (ref "R7") (pin "2") (pinfunction "2_2") (pintype "passive"))
    )
    (net (code "55") (name "Net-(IC2-L14)") (class "Default")
      (node (ref "IC2") (pin "21") (pinfunction "L14_21") (pintype "output"))
      (node (ref "R6") (pin "2") (pinfunction "2_2") (pintype "passive"))
    )
    (net (code "56") (name "Net-(IC2-L15)") (class "Default")
      (node (ref "IC2") (pin "22") (pinfunction "L15_22") (pintype "output"))
      (node (ref "R5") (pin "2") (pinfunction "2_2") (pintype "passive"))
    )
    (net (code "57") (name "SDI_MOSI") (class "Default")
      (node (ref "SERIAL") (pin "8") (pinfunction "8_8") (pintype "passive"))
    )
    (net (code "58") (name "SDI_SCLK") (class "Default")
      (node (ref "SERIAL") (pin "7") (pinfunction "7_7") (pintype "passive"))
    )
    (net (code "59") (name "SLIDER_IN") (class "Default")
      (node (ref "SERIAL") (pin "5") (pinfunction "5_5") (pintype "passive"))
    )
    (net (code "60") (name "unconnected-(B1-PadL3)") (class "Default")
      (node (ref "B1") (pin "L3") (pinfunction "L3_L3") (pintype "bidirectional"))
    )
    (net (code "61") (name "unconnected-(B1-PadL4)") (class "Default")
      (node (ref "B1") (pin "L4") (pinfunction "L4_L4") (pintype "bidirectional"))
    )
    (net (code "62") (name "unconnected-(B1-PadLC2)") (class "Default")
      (node (ref "B1") (pin "LC2") (pinfunction "LC2_LC2") (pintype "bidirectional"))
    )
    (net (code "63") (name "unconnected-(B2-PadL3)") (class "Default")
      (node (ref "B2") (pin "L3") (pinfunction "L3_L3") (pintype "bidirectional"))
    )
    (net (code "64") (name "unconnected-(B2-PadL4)") (class "Default")
      (node (ref "B2") (pin "L4") (pinfunction "L4_L4") (pintype "bidirectional"))
    )
    (net (code "65") (name "unconnected-(B2-PadLC2)") (class "Default")
      (node (ref "B2") (pin "LC2") (pinfunction "LC2_LC2") (pintype "bidirectional"))
    )
    (net (code "66") (name "unconnected-(B2ALT-PadL3)") (class "Default")
      (node (ref "B2ALT") (pin "L3") (pinfunction "L3_L3") (pintype "bidirectional"))
    )
    (net (code "67") (name "unconnected-(B2ALT-PadL4)") (class "Default")
      (node (ref "B2ALT") (pin "L4") (pinfunction "L4_L4") (pintype "bidirectional"))
    )
    (net (code "68") (name "unconnected-(B2ALT-PadLC2)") (class "Default")
      (node (ref "B2ALT") (pin "LC2") (pinfunction "LC2_LC2") (pintype "bidirectional"))
    )
    (net (code "69") (name "unconnected-(B3-PadL3)") (class "Default")
      (node (ref "B3") (pin "L3") (pinfunction "L3_L3") (pintype "bidirectional"))
    )
    (net (code "70") (name "unconnected-(B3-PadL4)") (class "Default")
      (node (ref "B3") (pin "L4") (pinfunction "L4_L4") (pintype "bidirectional"))
    )
    (net (code "71") (name "unconnected-(B3-PadLC2)") (class "Default")
      (node (ref "B3") (pin "LC2") (pinfunction "LC2_LC2") (pintype "bidirectional"))
    )
    (net (code "72") (name "unconnected-(B4-PadL3)") (class "Default")
      (node (ref "B4") (pin "L3") (pinfunction "L3_L3") (pintype "bidirectional"))
    )
    (net (code "73") (name "unconnected-(B4-PadL4)") (class "Default")
      (node (ref "B4") (pin "L4") (pinfunction "L4_L4") (pintype "bidirectional"))
    )
    (net (code "74") (name "unconnected-(B4-PadLC2)") (class "Default")
      (node (ref "B4") (pin "LC2") (pinfunction "LC2_LC2") (pintype "bidirectional"))
    )
    (net (code "75") (name "unconnected-(B4ALT-PadL3)") (class "Default")
      (node (ref "B4ALT") (pin "L3") (pinfunction "L3_L3") (pintype "bidirectional"))
    )
    (net (code "76") (name "unconnected-(B4ALT-PadL4)") (class "Default")
      (node (ref "B4ALT") (pin "L4") (pinfunction "L4_L4") (pintype "bidirectional"))
    )
    (net (code "77") (name "unconnected-(B4ALT-PadLC2)") (class "Default")
      (node (ref "B4ALT") (pin "LC2") (pinfunction "LC2_LC2") (pintype "bidirectional"))
    )
    (net (code "78") (name "unconnected-(B5-PadL3)") (class "Default")
      (node (ref "B5") (pin "L3") (pinfunction "L3_L3") (pintype "bidirectional"))
    )
    (net (code "79") (name "unconnected-(B5-PadL4)") (class "Default")
      (node (ref "B5") (pin "L4") (pinfunction "L4_L4") (pintype "bidirectional"))
    )
    (net (code "80") (name "unconnected-(B5-PadLC2)") (class "Default")
      (node (ref "B5") (pin "LC2") (pinfunction "LC2_LC2") (pintype "bidirectional"))
    )
    (net (code "81") (name "unconnected-(B6-PadL3)") (class "Default")
      (node (ref "B6") (pin "L3") (pinfunction "L3_L3") (pintype "bidirectional"))
    )
    (net (code "82") (name "unconnected-(B6-PadL4)") (class "Default")
      (node (ref "B6") (pin "L4") (pinfunction "L4_L4") (pintype "bidirectional"))
    )
    (net (code "83") (name "unconnected-(B6-PadLC2)") (class "Default")
      (node (ref "B6") (pin "LC2") (pinfunction "LC2_LC2") (pintype "bidirectional"))
    )
    (net (code "84") (name "unconnected-(B6ALT-PadL3)") (class "Default")
      (node (ref "B6ALT") (pin "L3") (pinfunction "L3_L3") (pintype "bidirectional"))
    )
    (net (code "85") (name "unconnected-(B6ALT-PadL4)") (class "Default")
      (node (ref "B6ALT") (pin "L4") (pinfunction "L4_L4") (pintype "bidirectional"))
    )
    (net (code "86") (name "unconnected-(B6ALT-PadLC2)") (class "Default")
      (node (ref "B6ALT") (pin "LC2") (pinfunction "LC2_LC2") (pintype "bidirectional"))
    )
    (net (code "87") (name "unconnected-(B7-PadL3)") (class "Default")
      (node (ref "B7") (pin "L3") (pinfunction "L3_L3") (pintype "bidirectional"))
    )
    (net (code "88") (name "unconnected-(B7-PadL4)") (class "Default")
      (node (ref "B7") (pin "L4") (pinfunction "L4_L4") (pintype "bidirectional"))
    )
    (net (code "89") (name "unconnected-(B7-PadLC2)") (class "Default")
      (node (ref "B7") (pin "LC2") (pinfunction "LC2_LC2") (pintype "bidirectional"))
    )
    (net (code "90") (name "unconnected-(B8-PadL3)") (class "Default")
      (node (ref "B8") (pin "L3") (pinfunction "L3_L3") (pintype "bidirectional"))
    )
    (net (code "91") (name "unconnected-(B8-PadL4)") (class "Default")
      (node (ref "B8") (pin "L4") (pinfunction "L4_L4") (pintype "bidirectional"))
    )
    (net (code "92") (name "unconnected-(B8-PadLC2)") (class "Default")
      (node (ref "B8") (pin "LC2") (pinfunction "LC2_LC2") (pintype "bidirectional"))
    )
    (net (code "93") (name "unconnected-(B8ALT-PadL3)") (class "Default")
      (node (ref "B8ALT") (pin "L3") (pinfunction "L3_L3") (pintype "bidirectional"))
    )
    (net (code "94") (name "unconnected-(B8ALT-PadL4)") (class "Default")
      (node (ref "B8ALT") (pin "L4") (pinfunction "L4_L4") (pintype "bidirectional"))
    )
    (net (code "95") (name "unconnected-(B8ALT-PadLC2)") (class "Default")
      (node (ref "B8ALT") (pin "LC2") (pinfunction "LC2_LC2") (pintype "bidirectional"))
    )
    (net (code "96") (name "unconnected-(B9-PadL3)") (class "Default")
      (node (ref "B9") (pin "L3") (pinfunction "L3_L3") (pintype "bidirectional"))
    )
    (net (code "97") (name "unconnected-(B9-PadL4)") (class "Default")
      (node (ref "B9") (pin "L4") (pinfunction "L4_L4") (pintype "bidirectional"))
    )
    (net (code "98") (name "unconnected-(B9-PadLC2)") (class "Default")
      (node (ref "B9") (pin "LC2") (pinfunction "LC2_LC2") (pintype "bidirectional"))
    )
    (net (code "99") (name "unconnected-(B10-PadL3)") (class "Default")
      (node (ref "B10") (pin "L3") (pinfunction "L3_L3") (pintype "bidirectional"))
    )
    (net (code "100") (name "unconnected-(B10-PadL4)") (class "Default")
      (node (ref "B10") (pin "L4") (pinfunction "L4_L4") (pintype "bidirectional"))
    )
    (net (code "101") (name "unconnected-(B10-PadLC2)") (class "Default")
      (node (ref "B10") (pin "LC2") (pinfunction "LC2_LC2") (pintype "bidirectional"))
    )
    (net (code "102") (name "unconnected-(B10ALT-PadL3)") (class "Default")
      (node (ref "B10ALT") (pin "L3") (pinfunction "L3_L3") (pintype "bidirectional"))
    )
    (net (code "103") (name "unconnected-(B10ALT-PadL4)") (class "Default")
      (node (ref "B10ALT") (pin "L4") (pinfunction "L4_L4") (pintype "bidirectional"))
    )
    (net (code "104") (name "unconnected-(B10ALT-PadLC2)") (class "Default")
      (node (ref "B10ALT") (pin "LC2") (pinfunction "LC2_LC2") (pintype "bidirectional"))
    )
    (net (code "105") (name "unconnected-(B11-PadL3)") (class "Default")
      (node (ref "B11") (pin "L3") (pinfunction "L3_L3") (pintype "bidirectional"))
    )
    (net (code "106") (name "unconnected-(B11-PadL4)") (class "Default")
      (node (ref "B11") (pin "L4") (pinfunction "L4_L4") (pintype "bidirectional"))
    )
    (net (code "107") (name "unconnected-(B11-PadLC2)") (class "Default")
      (node (ref "B11") (pin "LC2") (pinfunction "LC2_LC2") (pintype "bidirectional"))
    )
    (net (code "108") (name "unconnected-(B12-PadL3)") (class "Default")
      (node (ref "B12") (pin "L3") (pinfunction "L3_L3") (pintype "bidirectional"))
    )
    (net (code "109") (name "unconnected-(B12-PadL4)") (class "Default")
      (node (ref "B12") (pin "L4") (pinfunction "L4_L4") (pintype "bidirectional"))
    )
    (net (code "110") (name "unconnected-(B12-PadLC2)") (class "Default")
      (node (ref "B12") (pin "LC2") (pinfunction "LC2_LC2") (pintype "bidirectional"))
    )
    (net (code "111") (name "unconnected-(B12ALT-PadL3)") (class "Default")
      (node (ref "B12ALT") (pin "L3") (pinfunction "L3_L3") (pintype "bidirectional"))
    )
    (net (code "112") (name "unconnected-(B12ALT-PadL4)") (class "Default")
      (node (ref "B12ALT") (pin "L4") (pinfunction "L4_L4") (pintype "bidirectional"))
    )
    (net (code "113") (name "unconnected-(B12ALT-PadLC2)") (class "Default")
      (node (ref "B12ALT") (pin "LC2") (pinfunction "LC2_LC2") (pintype "bidirectional"))
    )
    (net (code "114") (name "unconnected-(B13-PadL3)") (class "Default")
      (node (ref "B13") (pin "L3") (pinfunction "L3_L3") (pintype "bidirectional"))
    )
    (net (code "115") (name "unconnected-(B13-PadL4)") (class "Default")
      (node (ref "B13") (pin "L4") (pinfunction "L4_L4") (pintype "bidirectional"))
    )
    (net (code "116") (name "unconnected-(B13-PadLC2)") (class "Default")
      (node (ref "B13") (pin "LC2") (pinfunction "LC2_LC2") (pintype "bidirectional"))
    )
    (net (code "117") (name "unconnected-(B14-PadL3)") (class "Default")
      (node (ref "B14") (pin "L3") (pinfunction "L3_L3") (pintype "bidirectional"))
    )
    (net (code "118") (name "unconnected-(B14-PadL4)") (class "Default")
      (node (ref "B14") (pin "L4") (pinfunction "L4_L4") (pintype "bidirectional"))
    )
    (net (code "119") (name "unconnected-(B14-PadLC2)") (class "Default")
      (node (ref "B14") (pin "LC2") (pinfunction "LC2_LC2") (pintype "bidirectional"))
    )
    (net (code "120") (name "unconnected-(B14ALT-PadL3)") (class "Default")
      (node (ref "B14ALT") (pin "L3") (pinfunction "L3_L3") (pintype "bidirectional"))
    )
    (net (code "121") (name "unconnected-(B14ALT-PadL4)") (class "Default")
      (node (ref "B14ALT") (pin "L4") (pinfunction "L4_L4") (pintype "bidirectional"))
    )
    (net (code "122") (name "unconnected-(B14ALT-PadLC2)") (class "Default")
      (node (ref "B14ALT") (pin "LC2") (pinfunction "LC2_LC2") (pintype "bidirectional"))
    )
    (net (code "123") (name "unconnected-(B15-PadL3)") (class "Default")
      (node (ref "B15") (pin "L3") (pinfunction "L3_L3") (pintype "bidirectional"))
    )
    (net (code "124") (name "unconnected-(B15-PadL4)") (class "Default")
      (node (ref "B15") (pin "L4") (pinfunction "L4_L4") (pintype "bidirectional"))
    )
    (net (code "125") (name "unconnected-(B15-PadLC2)") (class "Default")
      (node (ref "B15") (pin "LC2") (pinfunction "LC2_LC2") (pintype "bidirectional"))
    )
    (net (code "126") (name "unconnected-(B16-PadL3)") (class "Default")
      (node (ref "B16") (pin "L3") (pinfunction "L3_L3") (pintype "bidirectional"))
    )
    (net (code "127") (name "unconnected-(B16-PadL4)") (class "Default")
      (node (ref "B16") (pin "L4") (pinfunction "L4_L4") (pintype "bidirectional"))
    )
    (net (code "128") (name "unconnected-(B16-PadLC2)") (class "Default")
      (node (ref "B16") (pin "LC2") (pinfunction "LC2_LC2") (pintype "bidirectional"))
    )
    (net (code "129") (name "unconnected-(B16ALT-PadL3)") (class "Default")
      (node (ref "B16ALT") (pin "L3") (pinfunction "L3_L3") (pintype "bidirectional"))
    )
    (net (code "130") (name "unconnected-(B16ALT-PadL4)") (class "Default")
      (node (ref "B16ALT") (pin "L4") (pinfunction "L4_L4") (pintype "bidirectional"))
    )
    (net (code "131") (name "unconnected-(B16ALT-PadLC2)") (class "Default")
      (node (ref "B16ALT") (pin "LC2") (pinfunction "LC2_LC2") (pintype "bidirectional"))
    )
    (net (code "132") (name "unconnected-(IC1-INTA-Pad20)") (class "Default")
      (node (ref "IC1") (pin "20") (pinfunction "INTA_20") (pintype "output"))
    )
    (net (code "133") (name "unconnected-(IC1-INTB-Pad19)") (class "Default")
      (node (ref "IC1") (pin "19") (pinfunction "INTB_19") (pintype "output"))
    )
  )
)
